# main.net
KiCad netlist of a schematic drawn in EAGLE
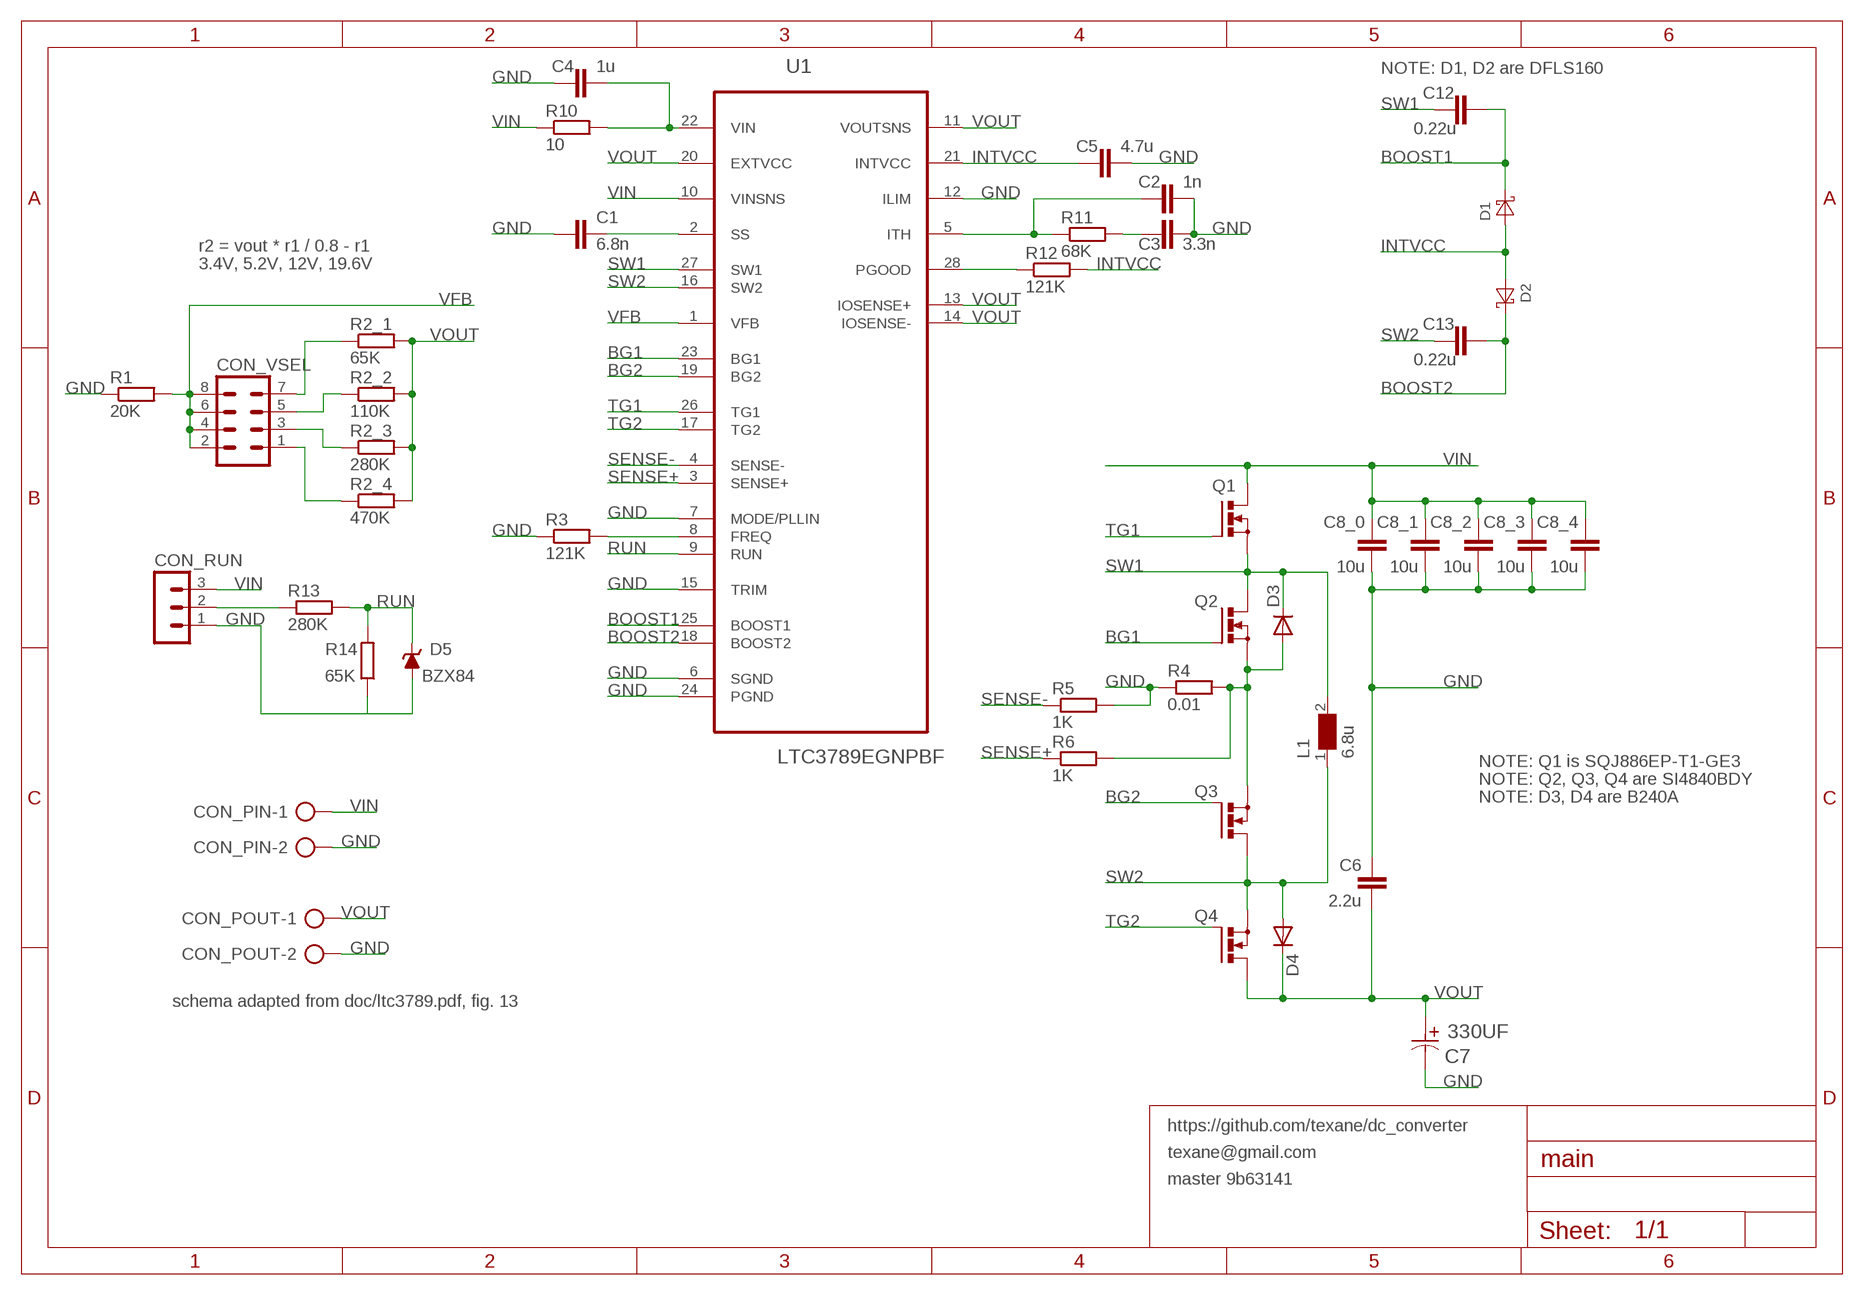
[diagram p0: schematic, sheet 1]

(export (version "E")
  (design (tool "Eeschema 10.0.6"))
  (components
    (comp (ref "C1")
      (value "6.8n")
      (footprint "eagle-import:C1206K")
      (libsource (lib "eagle-import") (part "C-EUC1206K"))
    )
    (comp (ref "C2")
      (value "1n")
      (footprint "eagle-import:C1206K")
      (libsource (lib "eagle-import") (part "C-EUC1206K"))
    )
    (comp (ref "C3")
      (value "3.3n")
      (footprint "eagle-import:C1206K")
      (libsource (lib "eagle-import") (part "C-EUC1206K"))
    )
    (comp (ref "C4")
      (value "1u")
      (footprint "eagle-import:C1206K")
      (libsource (lib "eagle-import") (part "C-EUC1206K"))
    )
    (comp (ref "C5")
      (value "4.7u")
      (footprint "eagle-import:C1206K")
      (libsource (lib "eagle-import") (part "C-EUC1206K"))
    )
    (comp (ref "C6")
      (value "2.2u")
      (footprint "eagle-import:C1206K")
      (libsource (lib "eagle-import") (part "C-EUC1206K"))
    )
    (comp (ref "C7")
      (value "330UF")
      (footprint "eagle-import:CAPAE1030X1050N")
      (fields (field (name "MPN") "EEE-FT1H331AP") (field (name "TOLERANCE") "±20 %"))
      (libsource (lib "eagle-import") (part "EEE--CASE-GFT1H331AP"))
    )
    (comp (ref "C8_0")
      (value "10u")
      (footprint "eagle-import:C1206K")
      (libsource (lib "eagle-import") (part "C-EUC1206K"))
    )
    (comp (ref "C8_1")
      (value "10u")
      (footprint "eagle-import:C1206K")
      (libsource (lib "eagle-import") (part "C-EUC1206K"))
    )
    (comp (ref "C8_2")
      (value "10u")
      (footprint "eagle-import:C1206K")
      (libsource (lib "eagle-import") (part "C-EUC1206K"))
    )
    (comp (ref "C8_3")
      (value "10u")
      (footprint "eagle-import:C1206K")
      (libsource (lib "eagle-import") (part "C-EUC1206K"))
    )
    (comp (ref "C8_4")
      (value "10u")
      (footprint "eagle-import:C1206K")
      (libsource (lib "eagle-import") (part "C-EUC1206K"))
    )
    (comp (ref "C12")
      (value "0.22u")
      (footprint "eagle-import:C1206K")
      (libsource (lib "eagle-import") (part "C-EUC1206K"))
    )
    (comp (ref "C13")
      (value "0.22u")
      (footprint "eagle-import:C1206K")
      (libsource (lib "eagle-import") (part "C-EUC1206K"))
    )
    (comp (ref "CON_PIN")
      (value "AK300/2")
      (footprint "eagle-import:AK300_2")
      (libsource (lib "eagle-import") (part "AK300/2"))
    )
    (comp (ref "CON_POUT")
      (value "AK300/2")
      (footprint "eagle-import:AK300_2")
      (libsource (lib "eagle-import") (part "AK300/2"))
    )
    (comp (ref "CON_RUN")
      (value "MA03-1")
      (footprint "eagle-import:MA03-1")
      (libsource (lib "eagle-import") (part "MA03-1"))
    )
    (comp (ref "CON_VSEL")
      (value "MA04-2")
      (footprint "eagle-import:MA04-2")
      (libsource (lib "eagle-import") (part "MA04-2"))
    )
    (comp (ref "D1")
      (value "DIODE-SCHOTTKY-POWER-DI-123")
      (footprint "eagle-import:POWER-DI-123")
      (libsource (lib "eagle-import") (part "DIODE-SCHOTTKY-POWER-DI-123"))
    )
    (comp (ref "D2")
      (value "DIODE-SCHOTTKY-POWER-DI-123")
      (footprint "eagle-import:POWER-DI-123")
      (libsource (lib "eagle-import") (part "DIODE-SCHOTTKY-POWER-DI-123"))
    )
    (comp (ref "D3")
      (value "DIODE-DO214AC")
      (footprint "eagle-import:DO214AC")
      (libsource (lib "eagle-import") (part "DIODE-DO214AC"))
    )
    (comp (ref "D4")
      (value "DIODE-DO214AC")
      (footprint "eagle-import:DO214AC")
      (libsource (lib "eagle-import") (part "DIODE-DO214AC"))
    )
    (comp (ref "D5")
      (value "BZX84")
      (footprint "eagle-import:SOT23")
      (libsource (lib "eagle-import") (part "BZX84"))
    )
    (comp (ref "L1")
      (value "6.8u")
      (footprint "eagle-import:WE-HCC_1210")
      (fields (field (name "MPN") "7443320680"))
      (libsource (lib "eagle-import") (part "WE-HCC_1210-7443320680"))
    )
    (comp (ref "Q1")
      (value "SQJ886EP")
      (footprint "eagle-import:POWERPAK-SO-08L")
      (libsource (lib "eagle-import") (part "SQJ886EP"))
    )
    (comp (ref "Q2")
      (value "N-MOSFET-SO8S")
      (footprint "eagle-import:SO-08")
      (libsource (lib "eagle-import") (part "N-MOSFET-SO8S"))
    )
    (comp (ref "Q3")
      (value "N-MOSFET-SO8S")
      (footprint "eagle-import:SO-08")
      (libsource (lib "eagle-import") (part "N-MOSFET-SO8S"))
    )
    (comp (ref "Q4")
      (value "N-MOSFET-SO8S")
      (footprint "eagle-import:SO-08")
      (libsource (lib "eagle-import") (part "N-MOSFET-SO8S"))
    )
    (comp (ref "R1")
      (value "20K")
      (footprint "eagle-import:R1206")
      (libsource (lib "eagle-import") (part "R-EU_R1206"))
    )
    (comp (ref "R2_1")
      (value "65K")
      (footprint "eagle-import:R1206")
      (libsource (lib "eagle-import") (part "R-EU_R1206"))
    )
    (comp (ref "R2_2")
      (value "110K")
      (footprint "eagle-import:R1206")
      (libsource (lib "eagle-import") (part "R-EU_R1206"))
    )
    (comp (ref "R2_3")
      (value "280K")
      (footprint "eagle-import:R1206")
      (libsource (lib "eagle-import") (part "R-EU_R1206"))
    )
    (comp (ref "R2_4")
      (value "470K")
      (footprint "eagle-import:R1206")
      (libsource (lib "eagle-import") (part "R-EU_R1206"))
    )
    (comp (ref "R3")
      (value "121K")
      (footprint "eagle-import:R1206")
      (libsource (lib "eagle-import") (part "R-EU_R1206"))
    )
    (comp (ref "R4")
      (value "0.01")
      (footprint "eagle-import:R1206")
      (libsource (lib "eagle-import") (part "R-EU_R1206"))
    )
    (comp (ref "R5")
      (value "1K")
      (footprint "eagle-import:R1206")
      (libsource (lib "eagle-import") (part "R-EU_R1206"))
    )
    (comp (ref "R6")
      (value "1K")
      (footprint "eagle-import:R1206")
      (libsource (lib "eagle-import") (part "R-EU_R1206"))
    )
    (comp (ref "R10")
      (value "10")
      (footprint "eagle-import:R1206")
      (libsource (lib "eagle-import") (part "R-EU_R1206"))
    )
    (comp (ref "R11")
      (value "68K")
      (footprint "eagle-import:R1206")
      (libsource (lib "eagle-import") (part "R-EU_R1206"))
    )
    (comp (ref "R12")
      (value "121K")
      (footprint "eagle-import:R1206")
      (libsource (lib "eagle-import") (part "R-EU_R1206"))
    )
    (comp (ref "R13")
      (value "280K")
      (footprint "eagle-import:R1206")
      (libsource (lib "eagle-import") (part "R-EU_R1206"))
    )
    (comp (ref "R14")
      (value "65K")
      (footprint "eagle-import:R1206")
      (libsource (lib "eagle-import") (part "R-EU_R1206"))
    )
    (comp (ref "U1")
      (value "LTC3789EGNPBF")
      (footprint "eagle-import:SOP65P640X120-28N")
      (fields (field (name "MPN") "LTC3789EGN#PBF"))
      (libsource (lib "eagle-import") (part "LTC3789EGNPBF"))
    )
  )
  (nets
    (net (code "1") (name "/BG1") (class "Default")
      (node (ref "Q2") (pin "4") (pinfunction "G_4") (pintype "passive"))
      (node (ref "U1") (pin "23") (pinfunction "BG1_23") (pintype "input"))
    )
    (net (code "2") (name "/BG2") (class "Default")
      (node (ref "Q3") (pin "4") (pinfunction "G_4") (pintype "passive"))
      (node (ref "U1") (pin "19") (pinfunction "BG2_19") (pintype "input"))
    )
    (net (code "3") (name "/BOOST1") (class "Default")
      (node (ref "C12") (pin "2") (pinfunction "2_2") (pintype "passive"))
      (node (ref "D1") (pin "C") (pinfunction "C_C") (pintype "passive"))
      (node (ref "U1") (pin "25") (pinfunction "BOOST1_25") (pintype "input"))
    )
    (net (code "4") (name "/BOOST2") (class "Default")
      (node (ref "C13") (pin "2") (pinfunction "2_2") (pintype "passive"))
      (node (ref "D2") (pin "C") (pinfunction "C_C") (pintype "passive"))
      (node (ref "U1") (pin "18") (pinfunction "BOOST2_18") (pintype "input"))
    )
    (net (code "5") (name "/GND") (class "Default")
      (node (ref "C1") (pin "1") (pinfunction "1_1") (pintype "passive"))
      (node (ref "C2") (pin "2") (pinfunction "2_2") (pintype "passive"))
      (node (ref "C3") (pin "2") (pinfunction "2_2") (pintype "passive"))
      (node (ref "C4") (pin "1") (pinfunction "1_1") (pintype "passive"))
      (node (ref "C5") (pin "2") (pinfunction "2_2") (pintype "passive"))
      (node (ref "C6") (pin "2") (pinfunction "2_2") (pintype "passive"))
      (node (ref "C7") (pin "2") (pinfunction "2_2") (pintype "passive"))
      (node (ref "C8_0") (pin "2") (pinfunction "2_2") (pintype "passive"))
      (node (ref "C8_1") (pin "2") (pinfunction "2_2") (pintype "passive"))
      (node (ref "C8_2") (pin "2") (pinfunction "2_2") (pintype "passive"))
      (node (ref "C8_3") (pin "2") (pinfunction "2_2") (pintype "passive"))
      (node (ref "C8_4") (pin "2") (pinfunction "2_2") (pintype "passive"))
      (node (ref "CON_PIN") (pin "2") (pinfunction "KL_2") (pintype "passive"))
      (node (ref "CON_POUT") (pin "2") (pinfunction "KL_2") (pintype "passive"))
      (node (ref "CON_RUN") (pin "1") (pinfunction "1_1") (pintype "passive"))
      (node (ref "D5") (pin "1") (pinfunction "A_1") (pintype "passive"))
      (node (ref "R1") (pin "1") (pinfunction "1_1") (pintype "passive"))
      (node (ref "R14") (pin "1") (pinfunction "1_1") (pintype "passive"))
      (node (ref "R3") (pin "1") (pinfunction "1_1") (pintype "passive"))
      (node (ref "R4") (pin "1") (pinfunction "1_1") (pintype "passive"))
      (node (ref "R5") (pin "2") (pinfunction "2_2") (pintype "passive"))
      (node (ref "U1") (pin "12") (pinfunction "ILIM_12") (pintype "bidirectional"))
      (node (ref "U1") (pin "15") (pinfunction "TRIM_15") (pintype "input"))
      (node (ref "U1") (pin "24") (pinfunction "PGND_24") (pintype "passive"))
      (node (ref "U1") (pin "6") (pinfunction "SGND_6") (pintype "passive"))
      (node (ref "U1") (pin "7") (pinfunction "MODE/PLLIN_7") (pintype "input"))
    )
    (net (code "6") (name "/INTVCC") (class "Default")
      (node (ref "C5") (pin "1") (pinfunction "1_1") (pintype "passive"))
      (node (ref "D1") (pin "A") (pinfunction "A_A") (pintype "passive"))
      (node (ref "D2") (pin "A") (pinfunction "A_A") (pintype "passive"))
      (node (ref "R12") (pin "2") (pinfunction "2_2") (pintype "passive"))
      (node (ref "U1") (pin "21") (pinfunction "INTVCC_21") (pintype "output"))
    )
    (net (code "7") (name "/RUN") (class "Default")
      (node (ref "D5") (pin "3") (pinfunction "C_3") (pintype "passive"))
      (node (ref "R13") (pin "2") (pinfunction "2_2") (pintype "passive"))
      (node (ref "R14") (pin "2") (pinfunction "2_2") (pintype "passive"))
      (node (ref "U1") (pin "9") (pinfunction "RUN_9") (pintype "input"))
    )
    (net (code "8") (name "/SENSE+") (class "Default")
      (node (ref "R6") (pin "1") (pinfunction "1_1") (pintype "passive"))
      (node (ref "U1") (pin "3") (pinfunction "SENSE+_3") (pintype "input"))
    )
    (net (code "9") (name "/SENSE-") (class "Default")
      (node (ref "R5") (pin "1") (pinfunction "1_1") (pintype "passive"))
      (node (ref "U1") (pin "4") (pinfunction "SENSE-_4") (pintype "input"))
    )
    (net (code "10") (name "/SW1") (class "Default")
      (node (ref "C12") (pin "1") (pinfunction "1_1") (pintype "passive"))
      (node (ref "D3") (pin "C") (pinfunction "C_C") (pintype "passive"))
      (node (ref "L1") (pin "2") (pinfunction "2_2") (pintype "passive"))
      (node (ref "Q1") (pin "1") (pinfunction "S_1") (pintype "passive"))
      (node (ref "Q1") (pin "2") (pinfunction "S_2") (pintype "passive"))
      (node (ref "Q1") (pin "3") (pinfunction "S_3") (pintype "passive"))
      (node (ref "Q2") (pin "5") (pinfunction "D_5") (pintype "passive"))
      (node (ref "Q2") (pin "6") (pinfunction "D_6") (pintype "passive"))
      (node (ref "Q2") (pin "7") (pinfunction "D_7") (pintype "passive"))
      (node (ref "Q2") (pin "8") (pinfunction "D_8") (pintype "passive"))
      (node (ref "U1") (pin "27") (pinfunction "SW1_27") (pintype "input"))
    )
    (net (code "11") (name "/SW2") (class "Default")
      (node (ref "C13") (pin "1") (pinfunction "1_1") (pintype "passive"))
      (node (ref "D4") (pin "A") (pinfunction "A_A") (pintype "passive"))
      (node (ref "L1") (pin "1") (pinfunction "1_1") (pintype "passive"))
      (node (ref "Q3") (pin "5") (pinfunction "D_5") (pintype "passive"))
      (node (ref "Q3") (pin "6") (pinfunction "D_6") (pintype "passive"))
      (node (ref "Q3") (pin "7") (pinfunction "D_7") (pintype "passive"))
      (node (ref "Q3") (pin "8") (pinfunction "D_8") (pintype "passive"))
      (node (ref "Q4") (pin "1") (pinfunction "S_1") (pintype "passive"))
      (node (ref "Q4") (pin "2") (pinfunction "S_2") (pintype "passive"))
      (node (ref "Q4") (pin "3") (pinfunction "S_3") (pintype "passive"))
      (node (ref "U1") (pin "16") (pinfunction "SW2_16") (pintype "input"))
    )
    (net (code "12") (name "/TG1") (class "Default")
      (node (ref "Q1") (pin "4") (pinfunction "G_4") (pintype "passive"))
      (node (ref "U1") (pin "26") (pinfunction "TG1_26") (pintype "input"))
    )
    (net (code "13") (name "/TG2") (class "Default")
      (node (ref "Q4") (pin "4") (pinfunction "G_4") (pintype "passive"))
      (node (ref "U1") (pin "17") (pinfunction "TG2_17") (pintype "input"))
    )
    (net (code "14") (name "/VFB") (class "Default")
      (node (ref "CON_VSEL") (pin "1") (pinfunction "1_1") (pintype "passive"))
      (node (ref "CON_VSEL") (pin "2") (pinfunction "2_2") (pintype "passive"))
      (node (ref "CON_VSEL") (pin "4") (pinfunction "4_4") (pintype "passive"))
      (node (ref "CON_VSEL") (pin "6") (pinfunction "6_6") (pintype "passive"))
      (node (ref "CON_VSEL") (pin "8") (pinfunction "8_8") (pintype "passive"))
      (node (ref "R1") (pin "2") (pinfunction "2_2") (pintype "passive"))
      (node (ref "R2_4") (pin "1") (pinfunction "1_1") (pintype "passive"))
      (node (ref "U1") (pin "1") (pinfunction "VFB_1") (pintype "input"))
    )
    (net (code "15") (name "/VIN") (class "Default")
      (node (ref "C8_0") (pin "1") (pinfunction "1_1") (pintype "passive"))
      (node (ref "C8_1") (pin "1") (pinfunction "1_1") (pintype "passive"))
      (node (ref "C8_2") (pin "1") (pinfunction "1_1") (pintype "passive"))
      (node (ref "C8_3") (pin "1") (pinfunction "1_1") (pintype "passive"))
      (node (ref "C8_4") (pin "1") (pinfunction "1_1") (pintype "passive"))
      (node (ref "CON_PIN") (pin "1") (pinfunction "KL_1") (pintype "passive"))
      (node (ref "CON_RUN") (pin "3") (pinfunction "3_3") (pintype "passive"))
      (node (ref "Q1") (pin "5-8") (pinfunction "D_5-8") (pintype "passive"))
      (node (ref "R10") (pin "1") (pinfunction "1_1") (pintype "passive"))
      (node (ref "U1") (pin "10") (pinfunction "VINSNS_10") (pintype "input"))
    )
    (net (code "16") (name "/VOUT") (class "Default")
      (node (ref "C6") (pin "1") (pinfunction "1_1") (pintype "passive"))
      (node (ref "C7") (pin "1") (pinfunction "1_1") (pintype "passive"))
      (node (ref "CON_POUT") (pin "1") (pinfunction "KL_1") (pintype "passive"))
      (node (ref "D4") (pin "C") (pinfunction "C_C") (pintype "passive"))
      (node (ref "Q4") (pin "5") (pinfunction "D_5") (pintype "passive"))
      (node (ref "Q4") (pin "6") (pinfunction "D_6") (pintype "passive"))
      (node (ref "Q4") (pin "7") (pinfunction "D_7") (pintype "passive"))
      (node (ref "Q4") (pin "8") (pinfunction "D_8") (pintype "passive"))
      (node (ref "R2_1") (pin "2") (pinfunction "2_2") (pintype "passive"))
      (node (ref "R2_2") (pin "2") (pinfunction "2_2") (pintype "passive"))
      (node (ref "R2_3") (pin "2") (pinfunction "2_2") (pintype "passive"))
      (node (ref "R2_4") (pin "2") (pinfunction "2_2") (pintype "passive"))
      (node (ref "U1") (pin "11") (pinfunction "VOUTSNS_11") (pintype "output"))
      (node (ref "U1") (pin "13") (pinfunction "IOSENSE+_13") (pintype "bidirectional"))
      (node (ref "U1") (pin "14") (pinfunction "IOSENSE-_14") (pintype "bidirectional"))
      (node (ref "U1") (pin "20") (pinfunction "EXTVCC_20") (pintype "power_in"))
    )
    (net (code "17") (name "Net-(C3-Pad1)") (class "Default")
      (node (ref "C3") (pin "1") (pinfunction "1_1") (pintype "passive"))
      (node (ref "R11") (pin "2") (pinfunction "2_2") (pintype "passive"))
    )
    (net (code "18") (name "Net-(CON_RUN-Pad2)") (class "Default")
      (node (ref "CON_RUN") (pin "2") (pinfunction "2_2") (pintype "passive"))
      (node (ref "R13") (pin "1") (pinfunction "1_1") (pintype "passive"))
    )
    (net (code "19") (name "Net-(CON_VSEL-Pad3)") (class "Default")
      (node (ref "CON_VSEL") (pin "3") (pinfunction "3_3") (pintype "passive"))
      (node (ref "R2_3") (pin "1") (pinfunction "1_1") (pintype "passive"))
    )
    (net (code "20") (name "Net-(CON_VSEL-Pad5)") (class "Default")
      (node (ref "CON_VSEL") (pin "5") (pinfunction "5_5") (pintype "passive"))
      (node (ref "R2_2") (pin "1") (pinfunction "1_1") (pintype "passive"))
    )
    (net (code "21") (name "Net-(CON_VSEL-Pad7)") (class "Default")
      (node (ref "CON_VSEL") (pin "7") (pinfunction "7_7") (pintype "passive"))
      (node (ref "R2_1") (pin "1") (pinfunction "1_1") (pintype "passive"))
    )
    (net (code "22") (name "Net-(D3-PadA)") (class "Default")
      (node (ref "D3") (pin "A") (pinfunction "A_A") (pintype "passive"))
      (node (ref "Q2") (pin "1") (pinfunction "S_1") (pintype "passive"))
      (node (ref "Q2") (pin "2") (pinfunction "S_2") (pintype "passive"))
      (node (ref "Q2") (pin "3") (pinfunction "S_3") (pintype "passive"))
      (node (ref "Q3") (pin "1") (pinfunction "S_1") (pintype "passive"))
      (node (ref "Q3") (pin "2") (pinfunction "S_2") (pintype "passive"))
      (node (ref "Q3") (pin "3") (pinfunction "S_3") (pintype "passive"))
      (node (ref "R4") (pin "2") (pinfunction "2_2") (pintype "passive"))
      (node (ref "R6") (pin "2") (pinfunction "2_2") (pintype "passive"))
    )
    (net (code "23") (name "Net-(U1-FREQ)") (class "Default")
      (node (ref "R3") (pin "2") (pinfunction "2_2") (pintype "passive"))
      (node (ref "U1") (pin "8") (pinfunction "FREQ_8") (pintype "input"))
    )
    (net (code "24") (name "Net-(U1-ITH)") (class "Default")
      (node (ref "C2") (pin "1") (pinfunction "1_1") (pintype "passive"))
      (node (ref "R11") (pin "1") (pinfunction "1_1") (pintype "passive"))
      (node (ref "U1") (pin "5") (pinfunction "ITH_5") (pintype "output"))
    )
    (net (code "25") (name "Net-(U1-PGOOD)") (class "Default")
      (node (ref "R12") (pin "1") (pinfunction "1_1") (pintype "passive"))
      (node (ref "U1") (pin "28") (pinfunction "PGOOD_28") (pintype "output"))
    )
    (net (code "26") (name "Net-(U1-SS)") (class "Default")
      (node (ref "C1") (pin "2") (pinfunction "2_2") (pintype "passive"))
      (node (ref "U1") (pin "2") (pinfunction "SS_2") (pintype "input"))
    )
    (net (code "27") (name "Net-(U1-VIN)") (class "Default")
      (node (ref "C4") (pin "2") (pinfunction "2_2") (pintype "passive"))
      (node (ref "R10") (pin "2") (pinfunction "2_2") (pintype "passive"))
      (node (ref "U1") (pin "22") (pinfunction "VIN_22") (pintype "power_in"))
    )
  )
)
